# 1__schdoc.net
KiCad netlist of a schematic drawn in Altium Designer
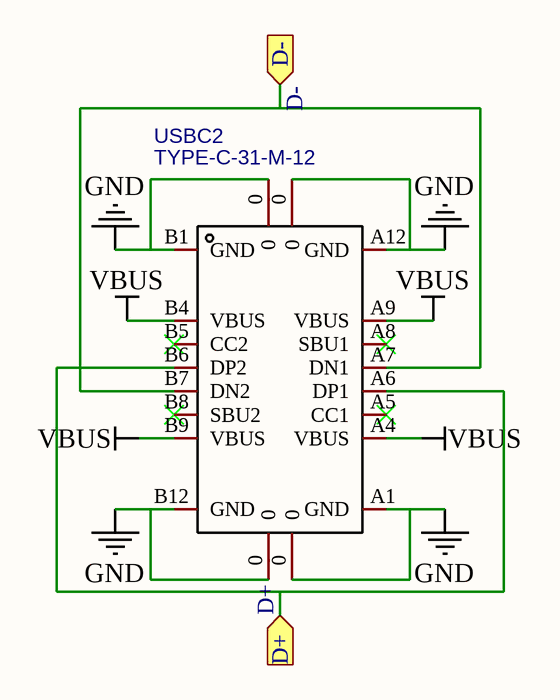
[diagram p0: 1_模块原理图.schdoc.schdoc]

(export (version "E")
  (design (tool "Eeschema 10.0.6"))
  (components
    (comp (ref "USBC2")
      (value "TYPE-C-31-M-12")
      (fields
        (field (name "NAME") "TYPE-C-31-M-12")
        (field (name "MANUFACTURER") "RectangularConnectors-Contacts")
      )
      (libsource (lib "altium-import") (part "root_0_TYPE-C-31-M-12_"))
    )
  )
  (nets
    (net (code "1") (name "/D+") (class "Default")
      (node (ref "USBC2") (pin "A6") (pinfunction "DP1_A6") (pintype "passive"))
      (node (ref "USBC2") (pin "B6") (pinfunction "DP2_B6") (pintype "passive"))
    )
    (net (code "2") (name "/D-") (class "Default")
      (node (ref "USBC2") (pin "A7") (pinfunction "DN1_A7") (pintype "passive"))
      (node (ref "USBC2") (pin "B7") (pinfunction "DN2_B7") (pintype "passive"))
    )
    (net (code "3") (name "GND") (class "Default")
      (node (ref "USBC2") (pin "0") (pinfunction "0_0") (pintype "passive"))
      (node (ref "USBC2") (pin "A1") (pinfunction "GND_A1") (pintype "passive"))
      (node (ref "USBC2") (pin "A12") (pinfunction "GND_A12") (pintype "passive"))
      (node (ref "USBC2") (pin "B1") (pinfunction "GND_B1") (pintype "passive"))
      (node (ref "USBC2") (pin "B12") (pinfunction "GND_B12") (pintype "passive"))
    )
    (net (code "4") (name "VBUS") (class "Default")
      (node (ref "USBC2") (pin "A4") (pinfunction "VBUS_A4") (pintype "passive"))
      (node (ref "USBC2") (pin "A9") (pinfunction "VBUS_A9") (pintype "passive"))
      (node (ref "USBC2") (pin "B4") (pinfunction "VBUS_B4") (pintype "passive"))
      (node (ref "USBC2") (pin "B9") (pinfunction "VBUS_B9") (pintype "passive"))
    )
    (net (code "5") (name "unconnected-(USBC2-CC1-PadA5)") (class "Default")
      (node (ref "USBC2") (pin "A5") (pinfunction "CC1_A5") (pintype "passive+no_connect"))
    )
    (net (code "6") (name "unconnected-(USBC2-CC2-PadB5)") (class "Default")
      (node (ref "USBC2") (pin "B5") (pinfunction "CC2_B5") (pintype "passive+no_connect"))
    )
    (net (code "7") (name "unconnected-(USBC2-SBU1-PadA8)") (class "Default")
      (node (ref "USBC2") (pin "A8") (pinfunction "SBU1_A8") (pintype "passive+no_connect"))
    )
    (net (code "8") (name "unconnected-(USBC2-SBU2-PadB8)") (class "Default")
      (node (ref "USBC2") (pin "B8") (pinfunction "SBU2_B8") (pintype "passive+no_connect"))
    )
  )
)
